# ADC-POWER_SUPPLY.net
KiCad netlist of a schematic drawn in Altium Designer
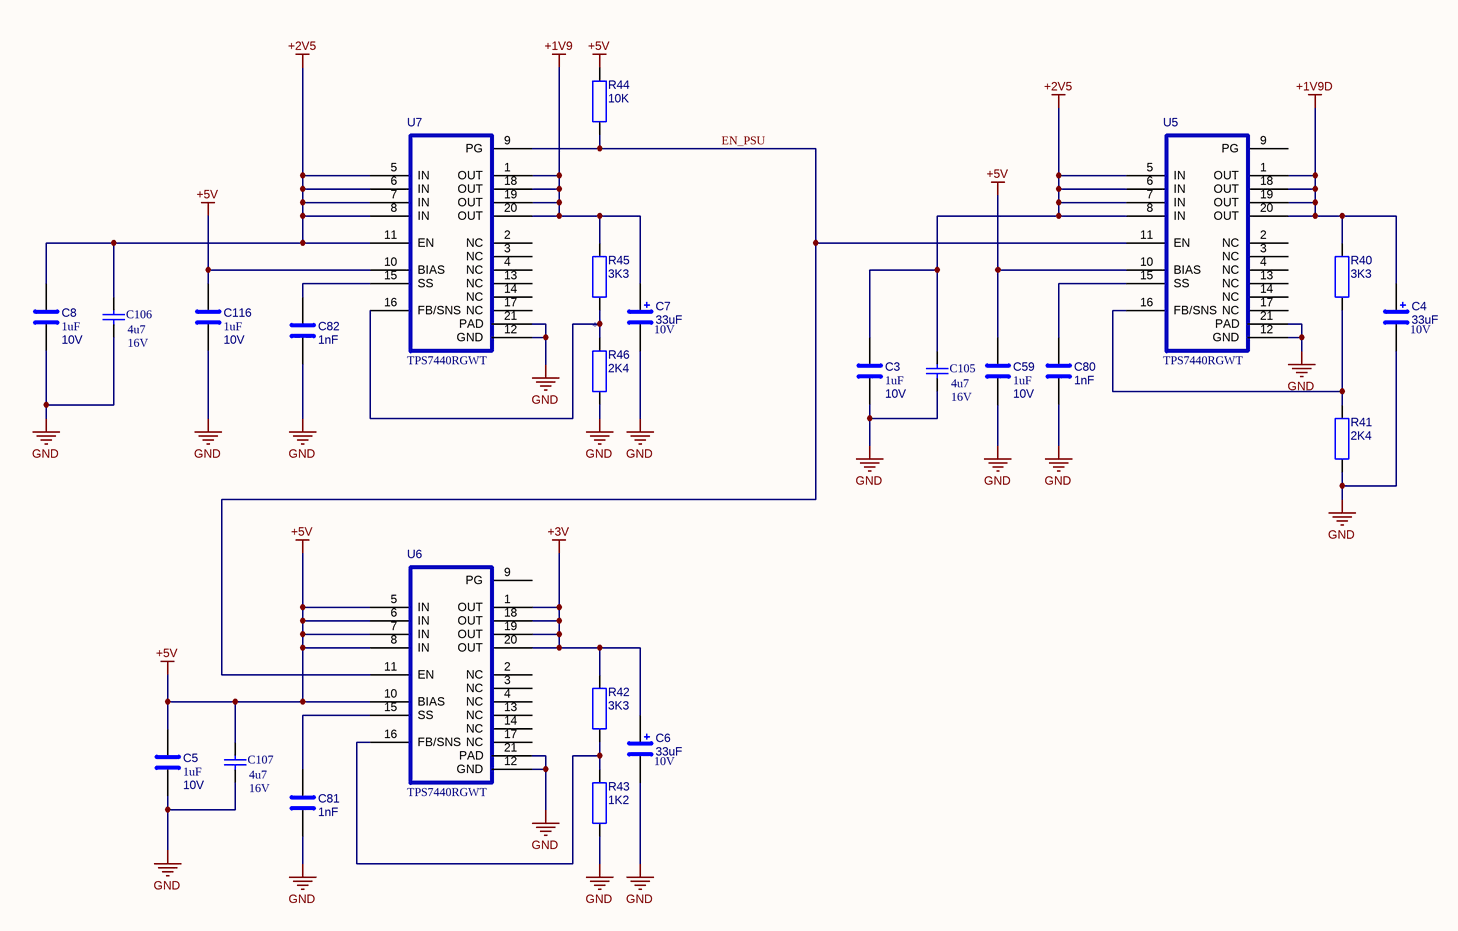
[diagram p0: ADC-POWER SUPPLY.SchDoc]

(export (version "E")
  (design (tool "Eeschema 10.0.6"))
  (components
    (comp (ref "C3")
      (value "10V")
      (footprint "CAPC1632X80USR")
      (description "CAP SMD 0603")
      (fields
        (field (name "VOLTAGE") "1uF")
        (field (name "Comment") "Footprint ???")
        (field (name "CREATED_BY") "*")
        (field (name "CHECKED_BY") "*")
      )
      (libsource (lib "Abdus-TEMP") (part "CAP-0603"))
    )
    (comp (ref "C4")
      (value "33uF")
      (footprint "3528")
      (description "CAPACITOR-POLARISED")
      (fields
        (field (name "VOLTAGE") "10V")
        (field (name "CREATED_BY") "EDA-ASA")
        (field (name "CHECKED_BY") "*")
      )
      (libsource (lib "EDA_GenericSymbols") (part "CAPACITOR-POLARISED"))
    )
    (comp (ref "C5")
      (value "10V")
      (footprint "CAPC1632X80USR")
      (description "CAP SMD 0603")
      (fields
        (field (name "VOLTAGE") "1uF")
        (field (name "Comment") "Footprint ???")
        (field (name "CREATED_BY") "*")
        (field (name "CHECKED_BY") "*")
      )
      (libsource (lib "Abdus-TEMP") (part "CAP-0603"))
    )
    (comp (ref "C6")
      (value "33uF")
      (footprint "3528")
      (description "CAPACITOR-POLARISED")
      (fields
        (field (name "VOLTAGE") "10V")
        (field (name "CREATED_BY") "EDA-ASA")
        (field (name "CHECKED_BY") "*")
      )
      (libsource (lib "EDA_GenericSymbols") (part "CAPACITOR-POLARISED"))
    )
    (comp (ref "C7")
      (value "33uF")
      (footprint "3528")
      (description "CAPACITOR-POLARISED")
      (fields
        (field (name "VOLTAGE") "10V")
        (field (name "CREATED_BY") "EDA-ASA")
        (field (name "CHECKED_BY") "*")
      )
      (libsource (lib "EDA_GenericSymbols") (part "CAPACITOR-POLARISED"))
    )
    (comp (ref "C8")
      (value "10V")
      (footprint "CAPC1632X80USR")
      (description "CAP SMD 0603")
      (fields
        (field (name "VOLTAGE") "1uF")
        (field (name "Comment") "Footprint ???")
        (field (name "CREATED_BY") "*")
        (field (name "CHECKED_BY") "*")
      )
      (libsource (lib "Abdus-TEMP") (part "CAP-0603"))
    )
    (comp (ref "C59")
      (value "10V")
      (footprint "CAPC1632X80USR")
      (description "CAP SMD 0603")
      (fields
        (field (name "VOLTAGE") "1uF")
        (field (name "Comment") "Footprint ???")
        (field (name "CREATED_BY") "*")
        (field (name "CHECKED_BY") "*")
      )
      (libsource (lib "Abdus-TEMP") (part "CAP-0603"))
    )
    (comp (ref "C80")
      (value "1nF")
      (footprint "0603")
      (description "CAP SMD 0603")
      (fields
        (field (name "Comment") "Footprint ???")
        (field (name "CREATED_BY") "*")
        (field (name "CHECKED_BY") "*")
      )
      (libsource (lib "Abdus-TEMP") (part "CAP-0603"))
    )
    (comp (ref "C81")
      (value "1nF")
      (footprint "0603")
      (description "CAP SMD 0603")
      (fields
        (field (name "Comment") "Footprint ???")
        (field (name "CREATED_BY") "*")
        (field (name "CHECKED_BY") "*")
      )
      (libsource (lib "Abdus-TEMP") (part "CAP-0603"))
    )
    (comp (ref "C82")
      (value "1nF")
      (footprint "0603")
      (description "CAP SMD 0603")
      (fields (field (name "CREATED_BY") "*") (field (name "CHECKED_BY") "*"))
      (libsource (lib "Abdus-TEMP") (part "CAP-0603"))
    )
    (comp (ref "C105")
      (value "4u7")
      (footprint "CAPC3225X220N")
      (description "Capacitor 1210 SMD")
      (fields
        (field (name "VOLTAGE") "16V")
        (field (name "CREATED_BY") "EDA-ASA")
        (field (name "CHECKED_BY") "*")
      )
      (libsource (lib "EDA-Passive") (part "cap1210"))
    )
    (comp (ref "C106")
      (value "4u7")
      (footprint "CAPC3225X220N")
      (description "Capacitor 1210 SMD")
      (fields
        (field (name "VOLTAGE") "16V")
        (field (name "CREATED_BY") "EDA-ASA")
        (field (name "CHECKED_BY") "*")
      )
      (libsource (lib "EDA-Passive") (part "cap1210"))
    )
    (comp (ref "C107")
      (value "4u7")
      (footprint "CAPC3225X220N")
      (description "Capacitor 1210 SMD")
      (fields
        (field (name "VOLTAGE") "16V")
        (field (name "CREATED_BY") "EDA-ASA")
        (field (name "CHECKED_BY") "*")
      )
      (libsource (lib "EDA-Passive") (part "cap1210"))
    )
    (comp (ref "C116")
      (value "10V")
      (footprint "CAPC1632X80USR")
      (description "CAP SMD 0603")
      (fields
        (field (name "VOLTAGE") "1uF")
        (field (name "Comment") "Footprint ???")
        (field (name "CREATED_BY") "*")
        (field (name "CHECKED_BY") "*")
      )
      (libsource (lib "Abdus-TEMP") (part "CAP-0603"))
    )
    (comp (ref "R40")
      (value "3K3")
      (footprint "0603")
      (description "RESISTOR SMD 0805")
      (fields (field (name "CREATED_BY") "*") (field (name "CHECKED_BY") "NN"))
      (libsource (lib "EDA_Passive") (part "RES-0805"))
    )
    (comp (ref "R41")
      (value "2K4")
      (footprint "0603")
      (description "RESISTOR SMD 0805")
      (fields (field (name "CREATED_BY") "*") (field (name "CHECKED_BY") "NN"))
      (libsource (lib "EDA_Passive") (part "RES-0805"))
    )
    (comp (ref "R42")
      (value "3K3")
      (footprint "0603")
      (description "RESISTOR SMD 0805")
      (fields (field (name "CREATED_BY") "*") (field (name "CHECKED_BY") "NN"))
      (libsource (lib "EDA_Passive") (part "RES-0805"))
    )
    (comp (ref "R43")
      (value "1K2")
      (footprint "0603")
      (description "RESISTOR SMD 0805")
      (fields (field (name "CREATED_BY") "*") (field (name "CHECKED_BY") "NN"))
      (libsource (lib "EDA_Passive") (part "RES-0805"))
    )
    (comp (ref "R44")
      (value "10K")
      (footprint "0603")
      (description "RESISTOR SMD 0805")
      (fields (field (name "CREATED_BY") "*") (field (name "CHECKED_BY") "NN"))
      (libsource (lib "EDA_Passive") (part "RES-0805"))
    )
    (comp (ref "R45")
      (value "3K3")
      (footprint "0603")
      (description "RESISTOR SMD 0805")
      (fields (field (name "CREATED_BY") "*") (field (name "CHECKED_BY") "NN"))
      (libsource (lib "EDA_Passive") (part "RES-0805"))
    )
    (comp (ref "R46")
      (value "2K4")
      (footprint "0603")
      (description "RESISTOR SMD 0805")
      (fields (field (name "WATTAGE") "*") (field (name "CREATED_BY") "*") (field (name "CHECKED_BY") "NN"))
      (libsource (lib "EDA_Passive") (part "RES-0805"))
    )
    (comp (ref "U5")
      (value "TPS7440RGWT")
      (footprint "QFN65P500X500X100-21AN")
      (description "3.0A Ultra-LDO with Programmable Soft-Start")
      (fields
        (field (name "MANUFACTURER") "TI")
        (field (name "CREATED_BY") "IN")
        (field (name "CHECKED_BY") "*")
      )
      (libsource (lib "Ishvah-TEMP") (part "TPS74401RGWT"))
    )
    (comp (ref "U6")
      (value "TPS7440RGWT")
      (footprint "QFN65P500X500X100-21AN")
      (description "3.0A Ultra-LDO with Programmable Soft-Start")
      (fields
        (field (name "MANUFACTURER") "TI")
        (field (name "CREATED_BY") "IN")
        (field (name "CHECKED_BY") "*")
      )
      (libsource (lib "Ishvah-TEMP") (part "TPS74401RGWT"))
    )
    (comp (ref "U7")
      (value "TPS7440RGWT")
      (footprint "QFN65P500X500X100-21AN")
      (description "3.0A Ultra-LDO with Programmable Soft-Start")
      (fields
        (field (name "MANUFACTURER") "TI")
        (field (name "CREATED_BY") "IN")
        (field (name "CHECKED_BY") "*")
      )
      (libsource (lib "Ishvah-TEMP") (part "TPS74401RGWT"))
    )
  )
  (nets
    (net (code "1") (name "+1V9") (class "Default")
      (node (ref "C7") (pin "1") (pinfunction "1_1") (pintype "passive"))
      (node (ref "R45") (pin "1") (pinfunction "1_1") (pintype "passive"))
      (node (ref "U7") (pin "1") (pinfunction "OUT_1") (pintype "passive"))
      (node (ref "U7") (pin "18") (pinfunction "OUT_18") (pintype "passive"))
      (node (ref "U7") (pin "19") (pinfunction "OUT_19") (pintype "passive"))
      (node (ref "U7") (pin "20") (pinfunction "OUT_20") (pintype "passive"))
    )
    (net (code "2") (name "+1V9D") (class "Default")
      (node (ref "C4") (pin "1") (pinfunction "1_1") (pintype "passive"))
      (node (ref "R40") (pin "1") (pinfunction "1_1") (pintype "passive"))
      (node (ref "U5") (pin "1") (pinfunction "OUT_1") (pintype "passive"))
      (node (ref "U5") (pin "18") (pinfunction "OUT_18") (pintype "passive"))
      (node (ref "U5") (pin "19") (pinfunction "OUT_19") (pintype "passive"))
      (node (ref "U5") (pin "20") (pinfunction "OUT_20") (pintype "passive"))
    )
    (net (code "3") (name "+2V5") (class "Default")
      (node (ref "C105") (pin "2") (pinfunction "2_2") (pintype "passive"))
      (node (ref "C106") (pin "2") (pinfunction "2_2") (pintype "passive"))
      (node (ref "C3") (pin "1") (pinfunction "1_1") (pintype "passive"))
      (node (ref "C8") (pin "1") (pinfunction "1_1") (pintype "passive"))
      (node (ref "U5") (pin "5") (pinfunction "IN_5") (pintype "passive"))
      (node (ref "U5") (pin "6") (pinfunction "IN_6") (pintype "passive"))
      (node (ref "U5") (pin "7") (pinfunction "IN_7") (pintype "passive"))
      (node (ref "U5") (pin "8") (pinfunction "IN_8") (pintype "passive"))
      (node (ref "U7") (pin "11") (pinfunction "EN_11") (pintype "passive"))
      (node (ref "U7") (pin "5") (pinfunction "IN_5") (pintype "passive"))
      (node (ref "U7") (pin "6") (pinfunction "IN_6") (pintype "passive"))
      (node (ref "U7") (pin "7") (pinfunction "IN_7") (pintype "passive"))
      (node (ref "U7") (pin "8") (pinfunction "IN_8") (pintype "passive"))
    )
    (net (code "4") (name "+3V") (class "Default")
      (node (ref "C6") (pin "1") (pinfunction "1_1") (pintype "passive"))
      (node (ref "R42") (pin "1") (pinfunction "1_1") (pintype "passive"))
      (node (ref "U6") (pin "1") (pinfunction "OUT_1") (pintype "passive"))
      (node (ref "U6") (pin "18") (pinfunction "OUT_18") (pintype "passive"))
      (node (ref "U6") (pin "19") (pinfunction "OUT_19") (pintype "passive"))
      (node (ref "U6") (pin "20") (pinfunction "OUT_20") (pintype "passive"))
    )
    (net (code "5") (name "+5V") (class "Default")
      (node (ref "C107") (pin "2") (pinfunction "2_2") (pintype "passive"))
      (node (ref "C116") (pin "1") (pinfunction "1_1") (pintype "passive"))
      (node (ref "C5") (pin "1") (pinfunction "1_1") (pintype "passive"))
      (node (ref "C59") (pin "1") (pinfunction "1_1") (pintype "passive"))
      (node (ref "R44") (pin "1") (pinfunction "1_1") (pintype "passive"))
      (node (ref "U5") (pin "10") (pinfunction "BIAS_10") (pintype "passive"))
      (node (ref "U6") (pin "10") (pinfunction "BIAS_10") (pintype "passive"))
      (node (ref "U6") (pin "5") (pinfunction "IN_5") (pintype "passive"))
      (node (ref "U6") (pin "6") (pinfunction "IN_6") (pintype "passive"))
      (node (ref "U6") (pin "7") (pinfunction "IN_7") (pintype "passive"))
      (node (ref "U6") (pin "8") (pinfunction "IN_8") (pintype "passive"))
      (node (ref "U7") (pin "10") (pinfunction "BIAS_10") (pintype "passive"))
    )
    (net (code "6") (name "/EN_PSU") (class "Default")
      (node (ref "R44") (pin "2") (pinfunction "2_2") (pintype "passive"))
      (node (ref "U5") (pin "11") (pinfunction "EN_11") (pintype "passive"))
      (node (ref "U6") (pin "11") (pinfunction "EN_11") (pintype "passive"))
      (node (ref "U7") (pin "9") (pinfunction "PG_9") (pintype "passive"))
    )
    (net (code "7") (name "GND") (class "Default")
      (node (ref "C105") (pin "1") (pinfunction "1_1") (pintype "passive"))
      (node (ref "C106") (pin "1") (pinfunction "1_1") (pintype "passive"))
      (node (ref "C107") (pin "1") (pinfunction "1_1") (pintype "passive"))
      (node (ref "C116") (pin "2") (pinfunction "2_2") (pintype "passive"))
      (node (ref "C3") (pin "2") (pinfunction "2_2") (pintype "passive"))
      (node (ref "C4") (pin "2") (pinfunction "2_2") (pintype "passive"))
      (node (ref "C5") (pin "2") (pinfunction "2_2") (pintype "passive"))
      (node (ref "C59") (pin "2") (pinfunction "2_2") (pintype "passive"))
      (node (ref "C6") (pin "2") (pinfunction "2_2") (pintype "passive"))
      (node (ref "C7") (pin "2") (pinfunction "2_2") (pintype "passive"))
      (node (ref "C8") (pin "2") (pinfunction "2_2") (pintype "passive"))
      (node (ref "C80") (pin "2") (pinfunction "2_2") (pintype "passive"))
      (node (ref "C81") (pin "2") (pinfunction "2_2") (pintype "passive"))
      (node (ref "C82") (pin "2") (pinfunction "2_2") (pintype "passive"))
      (node (ref "R41") (pin "1") (pinfunction "1_1") (pintype "passive"))
      (node (ref "R43") (pin "1") (pinfunction "1_1") (pintype "passive"))
      (node (ref "R46") (pin "1") (pinfunction "1_1") (pintype "passive"))
      (node (ref "U5") (pin "12") (pinfunction "GND_12") (pintype "passive"))
      (node (ref "U5") (pin "21") (pinfunction "PAD_21") (pintype "passive"))
      (node (ref "U6") (pin "12") (pinfunction "GND_12") (pintype "passive"))
      (node (ref "U6") (pin "21") (pinfunction "PAD_21") (pintype "passive"))
      (node (ref "U7") (pin "12") (pinfunction "GND_12") (pintype "passive"))
      (node (ref "U7") (pin "21") (pinfunction "PAD_21") (pintype "passive"))
    )
    (net (code "8") (name "Net-(U5-FB{slash}SNS)") (class "Default")
      (node (ref "R40") (pin "2") (pinfunction "2_2") (pintype "passive"))
      (node (ref "R41") (pin "2") (pinfunction "2_2") (pintype "passive"))
      (node (ref "U5") (pin "16") (pinfunction "FB/SNS_16") (pintype "passive"))
    )
    (net (code "9") (name "Net-(U5-SS)") (class "Default")
      (node (ref "C80") (pin "1") (pinfunction "1_1") (pintype "passive"))
      (node (ref "U5") (pin "15") (pinfunction "SS_15") (pintype "passive"))
    )
    (net (code "10") (name "Net-(U6-FB{slash}SNS)") (class "Default")
      (node (ref "R42") (pin "2") (pinfunction "2_2") (pintype "passive"))
      (node (ref "R43") (pin "2") (pinfunction "2_2") (pintype "passive"))
      (node (ref "U6") (pin "16") (pinfunction "FB/SNS_16") (pintype "passive"))
    )
    (net (code "11") (name "Net-(U6-SS)") (class "Default")
      (node (ref "C81") (pin "1") (pinfunction "1_1") (pintype "passive"))
      (node (ref "U6") (pin "15") (pinfunction "SS_15") (pintype "passive"))
    )
    (net (code "12") (name "Net-(U7-FB{slash}SNS)") (class "Default")
      (node (ref "R45") (pin "2") (pinfunction "2_2") (pintype "passive"))
      (node (ref "R46") (pin "2") (pinfunction "2_2") (pintype "passive"))
      (node (ref "U7") (pin "16") (pinfunction "FB/SNS_16") (pintype "passive"))
    )
    (net (code "13") (name "Net-(U7-SS)") (class "Default")
      (node (ref "C82") (pin "1") (pinfunction "1_1") (pintype "passive"))
      (node (ref "U7") (pin "15") (pinfunction "SS_15") (pintype "passive"))
    )
    (net (code "14") (name "unconnected-(U5-NC-Pad2)") (class "Default")
      (node (ref "U5") (pin "2") (pinfunction "NC_2") (pintype "passive"))
    )
    (net (code "15") (name "unconnected-(U5-NC-Pad3)") (class "Default")
      (node (ref "U5") (pin "3") (pinfunction "NC_3") (pintype "passive"))
    )
    (net (code "16") (name "unconnected-(U5-NC-Pad4)") (class "Default")
      (node (ref "U5") (pin "4") (pinfunction "NC_4") (pintype "passive"))
    )
    (net (code "17") (name "unconnected-(U5-NC-Pad13)") (class "Default")
      (node (ref "U5") (pin "13") (pinfunction "NC_13") (pintype "passive"))
    )
    (net (code "18") (name "unconnected-(U5-NC-Pad14)") (class "Default")
      (node (ref "U5") (pin "14") (pinfunction "NC_14") (pintype "passive"))
    )
    (net (code "19") (name "unconnected-(U5-NC-Pad17)") (class "Default")
      (node (ref "U5") (pin "17") (pinfunction "NC_17") (pintype "passive"))
    )
    (net (code "20") (name "unconnected-(U5-PG-Pad9)") (class "Default")
      (node (ref "U5") (pin "9") (pinfunction "PG_9") (pintype "passive"))
    )
    (net (code "21") (name "unconnected-(U6-NC-Pad2)") (class "Default")
      (node (ref "U6") (pin "2") (pinfunction "NC_2") (pintype "passive"))
    )
    (net (code "22") (name "unconnected-(U6-NC-Pad3)") (class "Default")
      (node (ref "U6") (pin "3") (pinfunction "NC_3") (pintype "passive"))
    )
    (net (code "23") (name "unconnected-(U6-NC-Pad4)") (class "Default")
      (node (ref "U6") (pin "4") (pinfunction "NC_4") (pintype "passive"))
    )
    (net (code "24") (name "unconnected-(U6-NC-Pad13)") (class "Default")
      (node (ref "U6") (pin "13") (pinfunction "NC_13") (pintype "passive"))
    )
    (net (code "25") (name "unconnected-(U6-NC-Pad14)") (class "Default")
      (node (ref "U6") (pin "14") (pinfunction "NC_14") (pintype "passive"))
    )
    (net (code "26") (name "unconnected-(U6-NC-Pad17)") (class "Default")
      (node (ref "U6") (pin "17") (pinfunction "NC_17") (pintype "passive"))
    )
    (net (code "27") (name "unconnected-(U6-PG-Pad9)") (class "Default")
      (node (ref "U6") (pin "9") (pinfunction "PG_9") (pintype "passive"))
    )
    (net (code "28") (name "unconnected-(U7-NC-Pad2)") (class "Default")
      (node (ref "U7") (pin "2") (pinfunction "NC_2") (pintype "passive"))
    )
    (net (code "29") (name "unconnected-(U7-NC-Pad3)") (class "Default")
      (node (ref "U7") (pin "3") (pinfunction "NC_3") (pintype "passive"))
    )
    (net (code "30") (name "unconnected-(U7-NC-Pad4)") (class "Default")
      (node (ref "U7") (pin "4") (pinfunction "NC_4") (pintype "passive"))
    )
    (net (code "31") (name "unconnected-(U7-NC-Pad13)") (class "Default")
      (node (ref "U7") (pin "13") (pinfunction "NC_13") (pintype "passive"))
    )
    (net (code "32") (name "unconnected-(U7-NC-Pad14)") (class "Default")
      (node (ref "U7") (pin "14") (pinfunction "NC_14") (pintype "passive"))
    )
    (net (code "33") (name "unconnected-(U7-NC-Pad17)") (class "Default")
      (node (ref "U7") (pin "17") (pinfunction "NC_17") (pintype "passive"))
    )
  )
)
